# ProjetoFinal.net
KiCad netlist of a schematic drawn in EAGLE
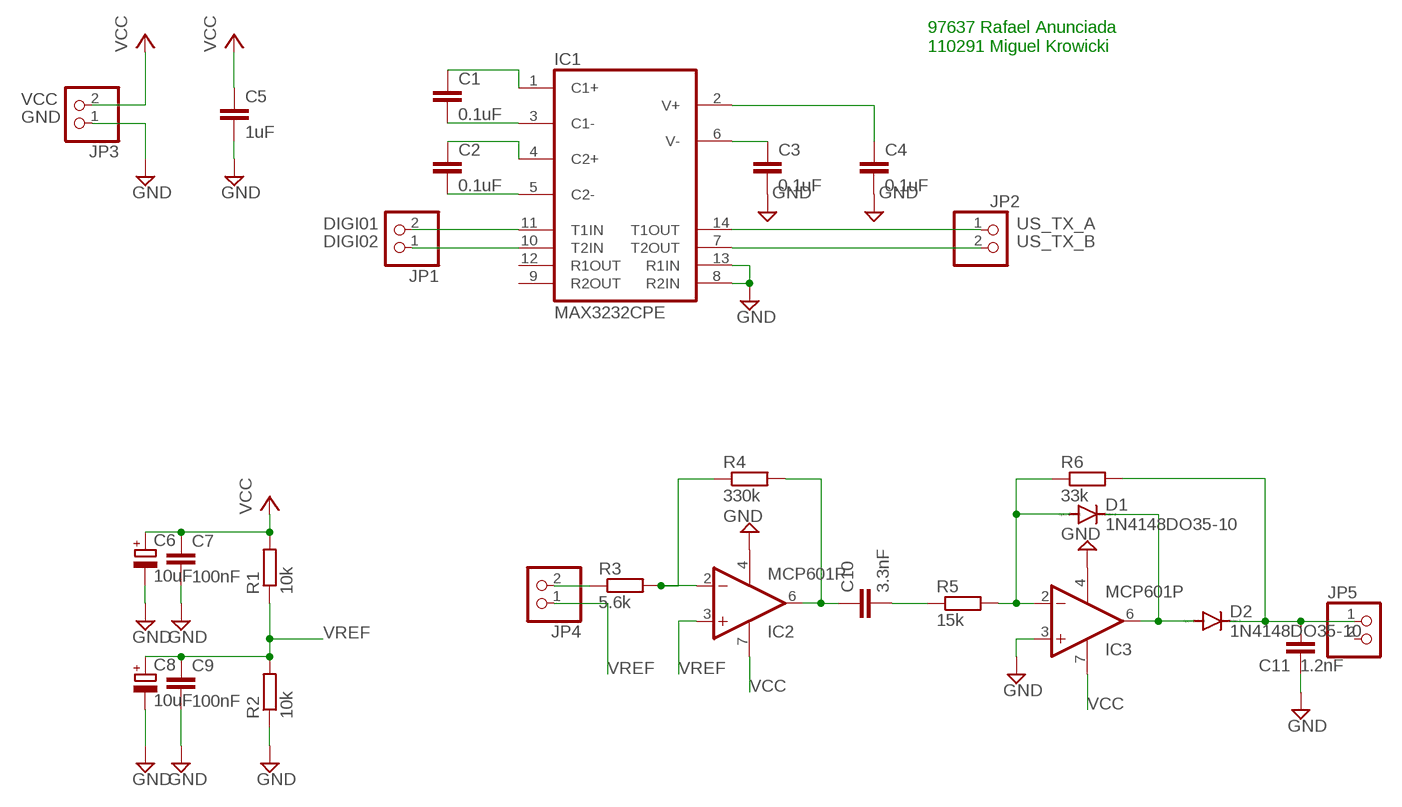
[diagram p0: schematic, sheet 1]

(export (version "E")
  (design (tool "Eeschema 10.0.6"))
  (components
    (comp (ref "C1")
      (value "0.1uF")
      (footprint "eagle-import:C025-025X050")
      (libsource (lib "eagle-import") (part "C-EU025-025X050"))
    )
    (comp (ref "C2")
      (value "0.1uF")
      (footprint "eagle-import:C025-025X050")
      (libsource (lib "eagle-import") (part "C-EU025-025X050"))
    )
    (comp (ref "C3")
      (value "0.1uF")
      (footprint "eagle-import:C025-025X050")
      (libsource (lib "eagle-import") (part "C-EU025-025X050"))
    )
    (comp (ref "C4")
      (value "0.1uF")
      (footprint "eagle-import:C025-025X050")
      (libsource (lib "eagle-import") (part "C-EU025-025X050"))
    )
    (comp (ref "C5")
      (value "1uF")
      (footprint "eagle-import:C025-025X050")
      (libsource (lib "eagle-import") (part "C-EU025-025X050"))
    )
    (comp (ref "C6")
      (value "10uF")
      (footprint "eagle-import:E2,5-6")
      (libsource (lib "eagle-import") (part "CPOL-EUE2.5-6"))
    )
    (comp (ref "C7")
      (value "100nF")
      (footprint "eagle-import:C025-025X050")
      (libsource (lib "eagle-import") (part "C-EU025-025X050"))
    )
    (comp (ref "C8")
      (value "10uF")
      (footprint "eagle-import:E2,5-6")
      (libsource (lib "eagle-import") (part "CPOL-EUE2.5-6"))
    )
    (comp (ref "C9")
      (value "100nF")
      (footprint "eagle-import:C025-025X050")
      (libsource (lib "eagle-import") (part "C-EU025-025X050"))
    )
    (comp (ref "C10")
      (value "3.3nF")
      (footprint "eagle-import:C025-025X050")
      (libsource (lib "eagle-import") (part "C-EU025-025X050"))
    )
    (comp (ref "C11")
      (value "1.2nF")
      (footprint "eagle-import:C025-025X050")
      (libsource (lib "eagle-import") (part "C-EU025-025X050"))
    )
    (comp (ref "D1")
      (value "1N4148DO35-10")
      (footprint "eagle-import:DO35-10")
      (libsource (lib "eagle-import") (part "1N4148DO35-10"))
    )
    (comp (ref "D2")
      (value "1N4148DO35-10")
      (footprint "eagle-import:DO35-10")
      (libsource (lib "eagle-import") (part "1N4148DO35-10"))
    )
    (comp (ref "IC1")
      (value "MAX3232CPE")
      (footprint "eagle-import:DIL16")
      (fields (field (name "MF") "MAXIM") (field (name "MPN") "MAX3232CPE+"))
      (libsource (lib "eagle-import") (part "MAX3232PEC"))
    )
    (comp (ref "IC2")
      (value "MCP601P")
      (footprint "eagle-import:DIL08")
      (libsource (lib "eagle-import") (part "MCP601P"))
    )
    (comp (ref "IC3")
      (value "MCP601P")
      (footprint "eagle-import:DIL08")
      (libsource (lib "eagle-import") (part "MCP601P"))
    )
    (comp (ref "JP1")
      (value "PINHD-1X2")
      (footprint "eagle-import:1X02")
      (libsource (lib "eagle-import") (part "PINHD-1X2"))
    )
    (comp (ref "JP2")
      (value "PINHD-1X2")
      (footprint "eagle-import:1X02")
      (libsource (lib "eagle-import") (part "PINHD-1X2"))
    )
    (comp (ref "JP3")
      (value "PINHD-1X2")
      (footprint "eagle-import:1X02")
      (libsource (lib "eagle-import") (part "PINHD-1X2"))
    )
    (comp (ref "JP4")
      (value "PINHD-1X2")
      (footprint "eagle-import:1X02")
      (libsource (lib "eagle-import") (part "PINHD-1X2"))
    )
    (comp (ref "JP5")
      (value "PINHD-1X2")
      (footprint "eagle-import:1X02")
      (libsource (lib "eagle-import") (part "PINHD-1X2"))
    )
    (comp (ref "R1")
      (value "10k")
      (footprint "eagle-import:0207_10")
      (libsource (lib "eagle-import") (part "R-EU_0207/10"))
    )
    (comp (ref "R2")
      (value "10k")
      (footprint "eagle-import:0207_10")
      (libsource (lib "eagle-import") (part "R-EU_0207/10"))
    )
    (comp (ref "R3")
      (value "5.6k")
      (footprint "eagle-import:0207_10")
      (libsource (lib "eagle-import") (part "R-EU_0207/10"))
    )
    (comp (ref "R4")
      (value "330k")
      (footprint "eagle-import:0207_10")
      (libsource (lib "eagle-import") (part "R-EU_0207/10"))
    )
    (comp (ref "R5")
      (value "15k")
      (footprint "eagle-import:0207_10")
      (libsource (lib "eagle-import") (part "R-EU_0207/10"))
    )
    (comp (ref "R6")
      (value "33k")
      (footprint "eagle-import:0207_10")
      (libsource (lib "eagle-import") (part "R-EU_0207/10"))
    )
  )
  (nets
    (net (code "1") (name "/DIGI01") (class "Default")
      (node (ref "IC1") (pin "11") (pinfunction "T1IN_11") (pintype "input"))
      (node (ref "JP1") (pin "2") (pinfunction "2_2") (pintype "passive"))
    )
    (net (code "2") (name "/DIGI02") (class "Default")
      (node (ref "IC1") (pin "10") (pinfunction "T2IN_10") (pintype "input"))
      (node (ref "JP1") (pin "1") (pinfunction "1_1") (pintype "passive"))
    )
    (net (code "3") (name "/US_TX_A") (class "Default")
      (node (ref "IC1") (pin "14") (pinfunction "T1OUT_14") (pintype "output"))
      (node (ref "JP2") (pin "1") (pinfunction "1_1") (pintype "passive"))
    )
    (net (code "4") (name "/US_TX_B") (class "Default")
      (node (ref "IC1") (pin "7") (pinfunction "T2OUT_7") (pintype "output"))
      (node (ref "JP2") (pin "2") (pinfunction "2_2") (pintype "passive"))
    )
    (net (code "5") (name "/VREF") (class "Default")
      (node (ref "C8") (pin "+") (pinfunction "+_+") (pintype "passive"))
      (node (ref "C9") (pin "1") (pinfunction "1_1") (pintype "passive"))
      (node (ref "IC2") (pin "3") (pinfunction "+IN_3") (pintype "input"))
      (node (ref "JP4") (pin "1") (pinfunction "1_1") (pintype "passive"))
      (node (ref "R1") (pin "1") (pinfunction "1_1") (pintype "passive"))
      (node (ref "R2") (pin "2") (pinfunction "2_2") (pintype "passive"))
    )
    (net (code "6") (name "GND") (class "Default")
      (node (ref "C11") (pin "1") (pinfunction "1_1") (pintype "passive"))
      (node (ref "C3") (pin "2") (pinfunction "2_2") (pintype "passive"))
      (node (ref "C4") (pin "2") (pinfunction "2_2") (pintype "passive"))
      (node (ref "C5") (pin "2") (pinfunction "2_2") (pintype "passive"))
      (node (ref "C6") (pin "-") (pinfunction "-_-") (pintype "passive"))
      (node (ref "C7") (pin "2") (pinfunction "2_2") (pintype "passive"))
      (node (ref "C8") (pin "-") (pinfunction "-_-") (pintype "passive"))
      (node (ref "C9") (pin "2") (pinfunction "2_2") (pintype "passive"))
      (node (ref "IC1") (pin "13") (pinfunction "R1IN_13") (pintype "input"))
      (node (ref "IC1") (pin "8") (pinfunction "R2IN_8") (pintype "input"))
      (node (ref "IC2") (pin "4") (pinfunction "V-_4") (pintype "power_in"))
      (node (ref "IC3") (pin "3") (pinfunction "+IN_3") (pintype "input"))
      (node (ref "IC3") (pin "4") (pinfunction "V-_4") (pintype "power_in"))
      (node (ref "JP3") (pin "1") (pinfunction "1_1") (pintype "passive"))
      (node (ref "R2") (pin "1") (pinfunction "1_1") (pintype "passive"))
    )
    (net (code "7") (name "Net-(C10-Pad2)") (class "Default")
      (node (ref "C10") (pin "2") (pinfunction "2_2") (pintype "passive"))
      (node (ref "R5") (pin "1") (pinfunction "1_1") (pintype "passive"))
    )
    (net (code "8") (name "Net-(C11-Pad2)") (class "Default")
      (node (ref "C11") (pin "2") (pinfunction "2_2") (pintype "passive"))
      (node (ref "D2") (pin "C") (pinfunction "C_C") (pintype "passive"))
      (node (ref "JP5") (pin "1") (pinfunction "1_1") (pintype "passive"))
      (node (ref "R6") (pin "2") (pinfunction "2_2") (pintype "passive"))
    )
    (net (code "9") (name "Net-(IC1A-C1+)") (class "Default")
      (node (ref "C1") (pin "1") (pinfunction "1_1") (pintype "passive"))
      (node (ref "IC1") (pin "1") (pinfunction "C1+_1") (pintype "bidirectional"))
    )
    (net (code "10") (name "Net-(IC1A-C1-)") (class "Default")
      (node (ref "C1") (pin "2") (pinfunction "2_2") (pintype "passive"))
      (node (ref "IC1") (pin "3") (pinfunction "C1-_3") (pintype "bidirectional"))
    )
    (net (code "11") (name "Net-(IC1A-C2+)") (class "Default")
      (node (ref "C2") (pin "1") (pinfunction "1_1") (pintype "passive"))
      (node (ref "IC1") (pin "4") (pinfunction "C2+_4") (pintype "bidirectional"))
    )
    (net (code "12") (name "Net-(IC1A-C2-)") (class "Default")
      (node (ref "C2") (pin "2") (pinfunction "2_2") (pintype "passive"))
      (node (ref "IC1") (pin "5") (pinfunction "C2-_5") (pintype "bidirectional"))
    )
    (net (code "13") (name "Net-(IC1A-V+)") (class "Default")
      (node (ref "C4") (pin "1") (pinfunction "1_1") (pintype "passive"))
      (node (ref "IC1") (pin "2") (pinfunction "V+_2") (pintype "bidirectional"))
    )
    (net (code "14") (name "Net-(IC1A-V-)") (class "Default")
      (node (ref "C3") (pin "1") (pinfunction "1_1") (pintype "passive"))
      (node (ref "IC1") (pin "6") (pinfunction "V-_6") (pintype "bidirectional"))
    )
    (net (code "15") (name "Net-(IC2--IN)") (class "Default")
      (node (ref "IC2") (pin "2") (pinfunction "-IN_2") (pintype "input"))
      (node (ref "R3") (pin "2") (pinfunction "2_2") (pintype "passive"))
      (node (ref "R4") (pin "1") (pinfunction "1_1") (pintype "passive"))
    )
    (net (code "16") (name "Net-(IC2-OUT)") (class "Default")
      (node (ref "C10") (pin "1") (pinfunction "1_1") (pintype "passive"))
      (node (ref "IC2") (pin "6") (pinfunction "OUT_6") (pintype "output"))
      (node (ref "R4") (pin "2") (pinfunction "2_2") (pintype "passive"))
    )
    (net (code "17") (name "Net-(IC3--IN)") (class "Default")
      (node (ref "D1") (pin "A") (pinfunction "A_A") (pintype "passive"))
      (node (ref "IC3") (pin "2") (pinfunction "-IN_2") (pintype "input"))
      (node (ref "R5") (pin "2") (pinfunction "2_2") (pintype "passive"))
      (node (ref "R6") (pin "1") (pinfunction "1_1") (pintype "passive"))
    )
    (net (code "18") (name "Net-(IC3-OUT)") (class "Default")
      (node (ref "D1") (pin "C") (pinfunction "C_C") (pintype "passive"))
      (node (ref "D2") (pin "A") (pinfunction "A_A") (pintype "passive"))
      (node (ref "IC3") (pin "6") (pinfunction "OUT_6") (pintype "output"))
    )
    (net (code "19") (name "Net-(JP4-Pad2)") (class "Default")
      (node (ref "JP4") (pin "2") (pinfunction "2_2") (pintype "passive"))
      (node (ref "R3") (pin "1") (pinfunction "1_1") (pintype "passive"))
    )
    (net (code "20") (name "VCC") (class "Default")
      (node (ref "C5") (pin "1") (pinfunction "1_1") (pintype "passive"))
      (node (ref "C6") (pin "+") (pinfunction "+_+") (pintype "passive"))
      (node (ref "C7") (pin "1") (pinfunction "1_1") (pintype "passive"))
      (node (ref "IC2") (pin "7") (pinfunction "V+_7") (pintype "power_in"))
      (node (ref "IC3") (pin "7") (pinfunction "V+_7") (pintype "power_in"))
      (node (ref "JP3") (pin "2") (pinfunction "2_2") (pintype "passive"))
      (node (ref "R1") (pin "2") (pinfunction "2_2") (pintype "passive"))
    )
    (net (code "21") (name "unconnected-(IC1A-R1OUT-Pad12)") (class "Default")
      (node (ref "IC1") (pin "12") (pinfunction "R1OUT_12") (pintype "output"))
    )
    (net (code "22") (name "unconnected-(IC1A-R2OUT-Pad9)") (class "Default")
      (node (ref "IC1") (pin "9") (pinfunction "R2OUT_9") (pintype "output"))
    )
    (net (code "23") (name "unconnected-(JP5-Pad2)") (class "Default")
      (node (ref "JP5") (pin "2") (pinfunction "2_2") (pintype "passive"))
    )
  )
)
